# cert3d_rev1.net
KiCad netlist of a schematic drawn in EAGLE
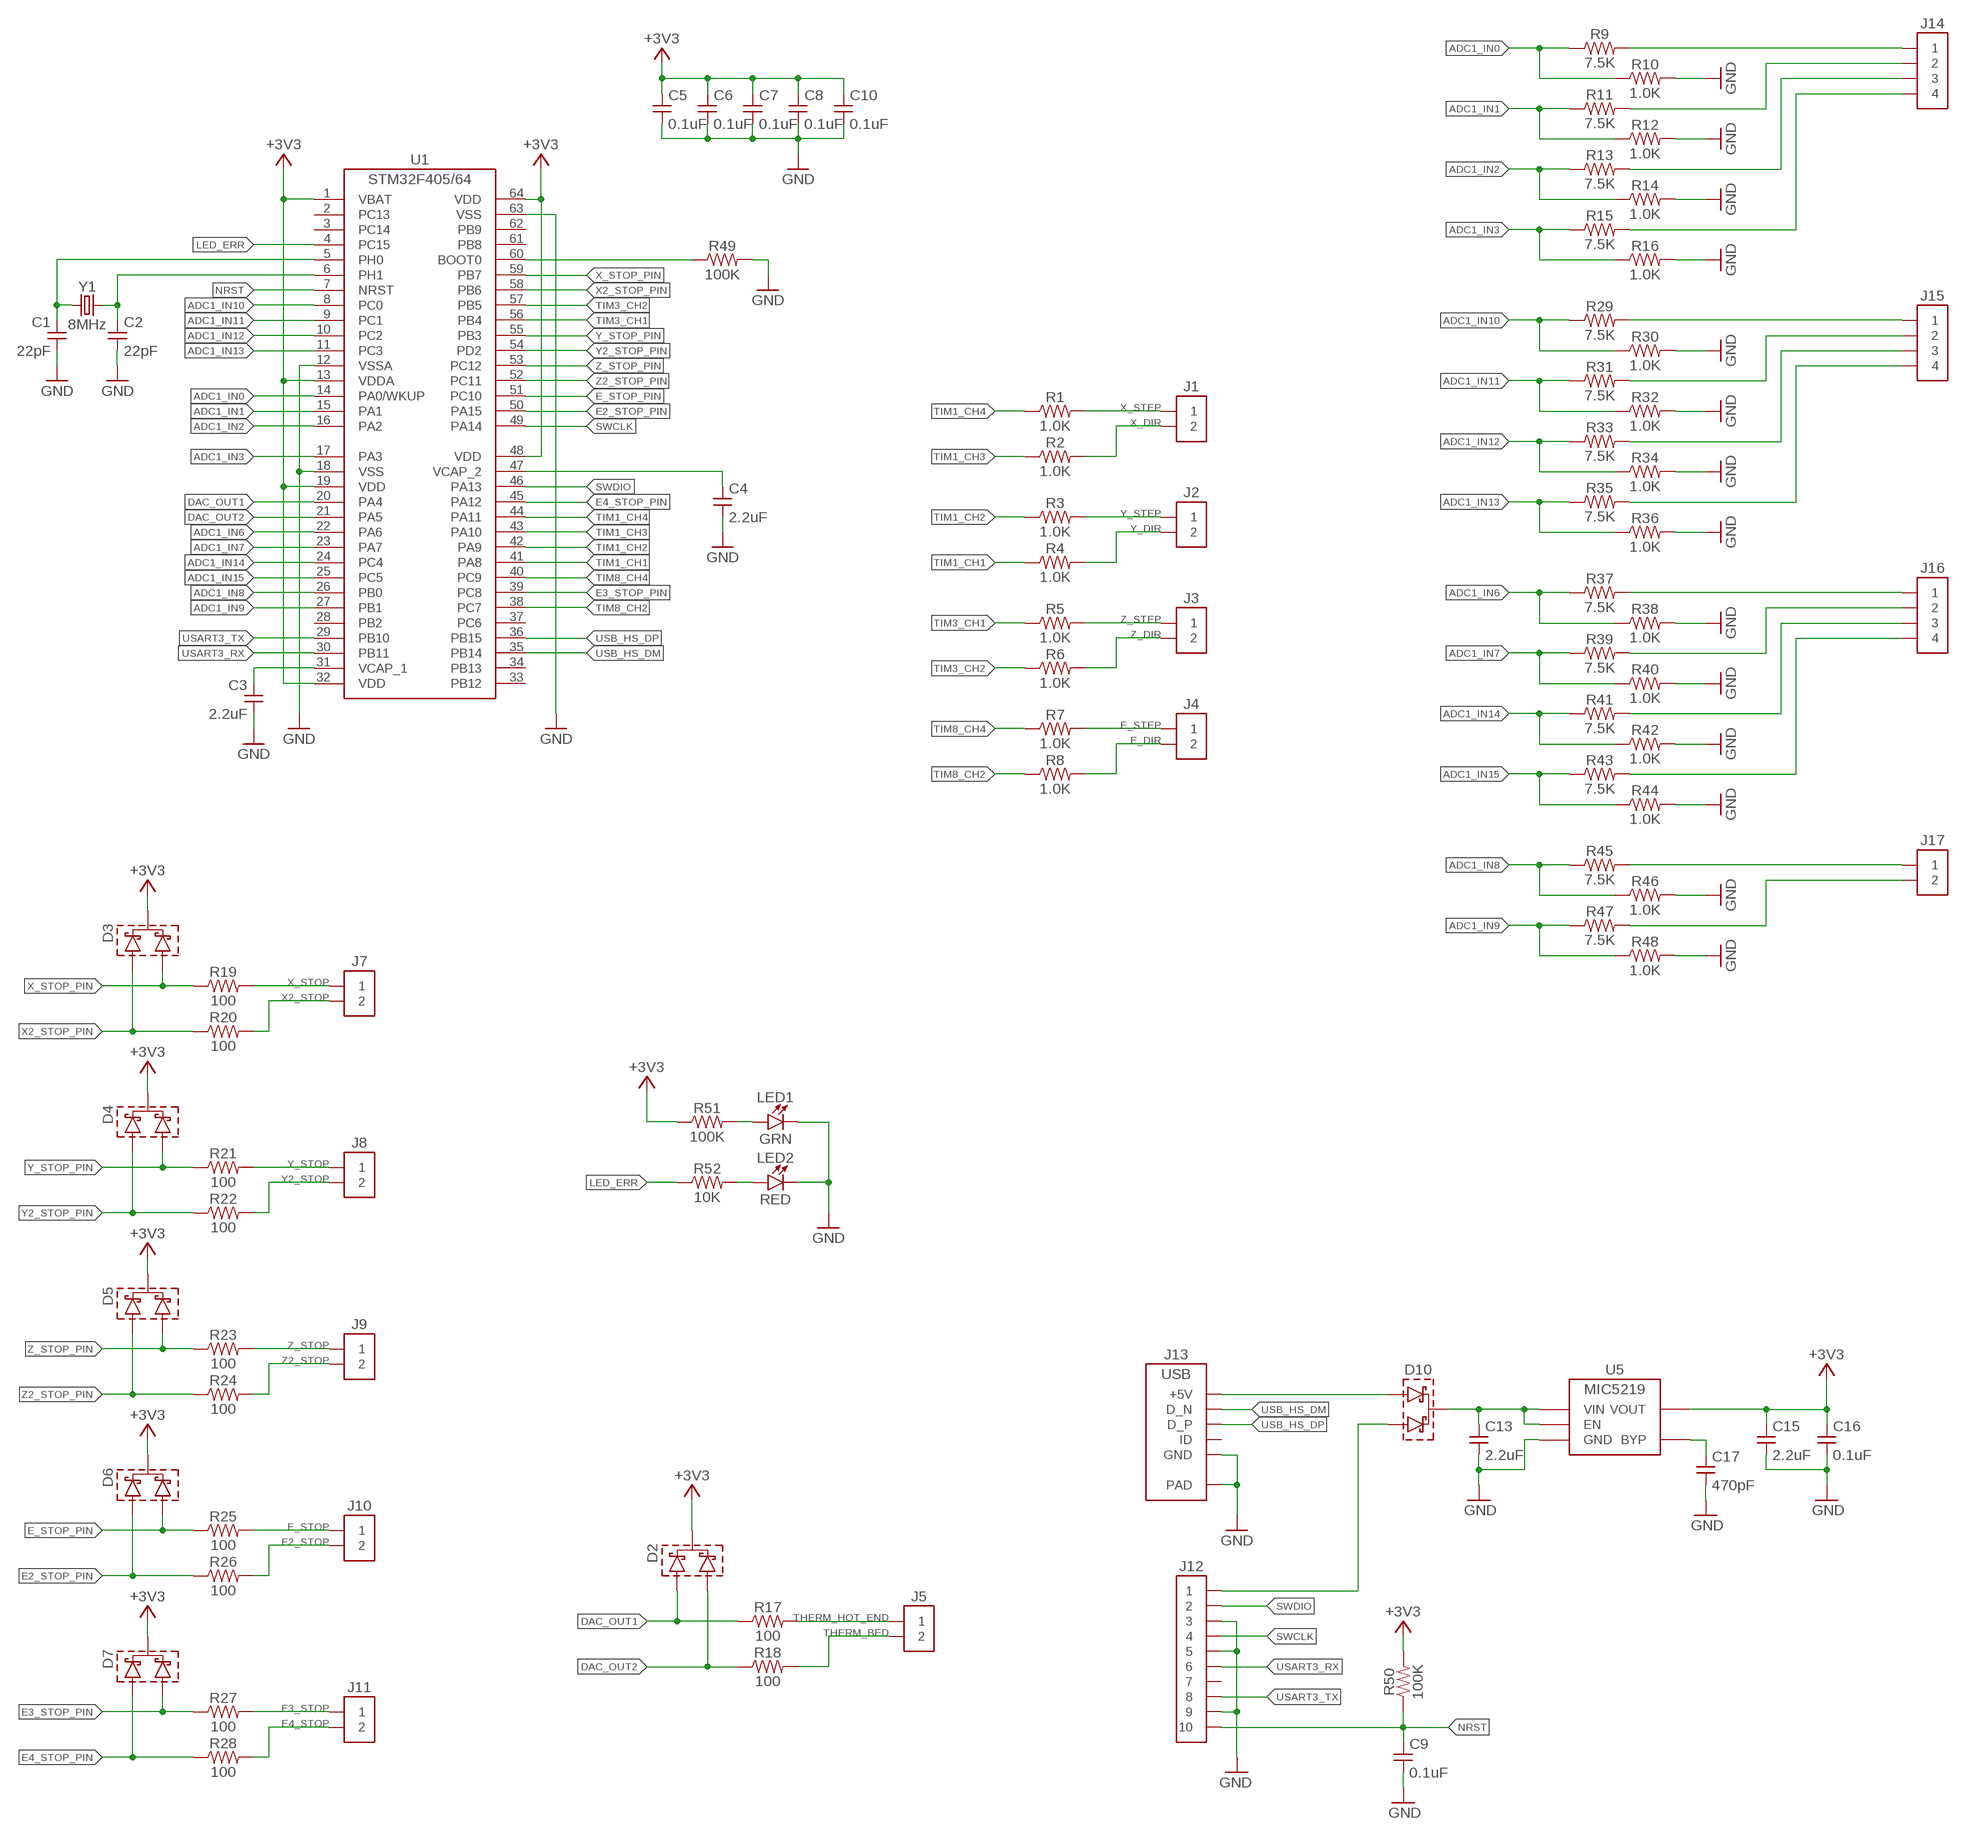
[diagram p0: schematic, sheet 1]

(export (version "E")
  (design (tool "Eeschema 10.0.6"))
  (components
    (comp (ref "C1")
      (value "22pF")
      (footprint "eagle-import:C0805-5MIL")
      (libsource (lib "eagle-import") (part "C_USC0805-5MIL"))
    )
    (comp (ref "C2")
      (value "22pF")
      (footprint "eagle-import:C0805-5MIL")
      (libsource (lib "eagle-import") (part "C_USC0805-5MIL"))
    )
    (comp (ref "C3")
      (value "2.2uF")
      (footprint "eagle-import:C0805-5MIL")
      (libsource (lib "eagle-import") (part "C_USC0805-5MIL"))
    )
    (comp (ref "C4")
      (value "2.2uF")
      (footprint "eagle-import:C0805-5MIL")
      (libsource (lib "eagle-import") (part "C_USC0805-5MIL"))
    )
    (comp (ref "C5")
      (value "0.1uF")
      (footprint "eagle-import:C0805-5MIL")
      (libsource (lib "eagle-import") (part "C_USC0805-5MIL"))
    )
    (comp (ref "C6")
      (value "0.1uF")
      (footprint "eagle-import:C0805-5MIL")
      (libsource (lib "eagle-import") (part "C_USC0805-5MIL"))
    )
    (comp (ref "C7")
      (value "0.1uF")
      (footprint "eagle-import:C0805-5MIL")
      (libsource (lib "eagle-import") (part "C_USC0805-5MIL"))
    )
    (comp (ref "C8")
      (value "0.1uF")
      (footprint "eagle-import:C0805-5MIL")
      (libsource (lib "eagle-import") (part "C_USC0805-5MIL"))
    )
    (comp (ref "C9")
      (value "0.1uF")
      (footprint "eagle-import:C0805-5MIL")
      (libsource (lib "eagle-import") (part "C_USC0805-5MIL"))
    )
    (comp (ref "C10")
      (value "0.1uF")
      (footprint "eagle-import:C0805-5MIL")
      (libsource (lib "eagle-import") (part "C_USC0805-5MIL"))
    )
    (comp (ref "C13")
      (value "2.2uF")
      (footprint "eagle-import:C0805-5MIL")
      (libsource (lib "eagle-import") (part "C_USC0805-5MIL"))
    )
    (comp (ref "C15")
      (value "2.2uF")
      (footprint "eagle-import:C0805-5MIL")
      (libsource (lib "eagle-import") (part "C_USC0805-5MIL"))
    )
    (comp (ref "C16")
      (value "0.1uF")
      (footprint "eagle-import:C0805-5MIL")
      (libsource (lib "eagle-import") (part "C_USC0805-5MIL"))
    )
    (comp (ref "C17")
      (value "470pF")
      (footprint "eagle-import:C0805-5MIL")
      (libsource (lib "eagle-import") (part "C_USC0805-5MIL"))
    )
    (comp (ref "D2")
      (value "SCHOTTKY_DUAL_CCBAT54C")
      (footprint "eagle-import:SOT23-3")
      (libsource (lib "eagle-import") (part "SCHOTTKY_DUAL_CCBAT54C"))
    )
    (comp (ref "D3")
      (value "SCHOTTKY_DUAL_CCBAT54C")
      (footprint "eagle-import:SOT23-3")
      (libsource (lib "eagle-import") (part "SCHOTTKY_DUAL_CCBAT54C"))
    )
    (comp (ref "D4")
      (value "SCHOTTKY_DUAL_CCBAT54C")
      (footprint "eagle-import:SOT23-3")
      (libsource (lib "eagle-import") (part "SCHOTTKY_DUAL_CCBAT54C"))
    )
    (comp (ref "D5")
      (value "SCHOTTKY_DUAL_CCBAT54C")
      (footprint "eagle-import:SOT23-3")
      (libsource (lib "eagle-import") (part "SCHOTTKY_DUAL_CCBAT54C"))
    )
    (comp (ref "D6")
      (value "SCHOTTKY_DUAL_CCBAT54C")
      (footprint "eagle-import:SOT23-3")
      (libsource (lib "eagle-import") (part "SCHOTTKY_DUAL_CCBAT54C"))
    )
    (comp (ref "D7")
      (value "SCHOTTKY_DUAL_CCBAT54C")
      (footprint "eagle-import:SOT23-3")
      (libsource (lib "eagle-import") (part "SCHOTTKY_DUAL_CCBAT54C"))
    )
    (comp (ref "D10")
      (value "SCHOTTKY_DUAL_CCBAT54C")
      (footprint "eagle-import:SOT23-3")
      (libsource (lib "eagle-import") (part "SCHOTTKY_DUAL_CCBAT54C"))
    )
    (comp (ref "J1")
      (value "CONN2TSW-S")
      (footprint "eagle-import:SAM-TSW-102-XX-X-S")
      (libsource (lib "eagle-import") (part "CONN2TSW-S"))
    )
    (comp (ref "J2")
      (value "CONN2TSW-S")
      (footprint "eagle-import:SAM-TSW-102-XX-X-S")
      (libsource (lib "eagle-import") (part "CONN2TSW-S"))
    )
    (comp (ref "J3")
      (value "CONN2TSW-S")
      (footprint "eagle-import:SAM-TSW-102-XX-X-S")
      (libsource (lib "eagle-import") (part "CONN2TSW-S"))
    )
    (comp (ref "J4")
      (value "CONN2TSW-S")
      (footprint "eagle-import:SAM-TSW-102-XX-X-S")
      (libsource (lib "eagle-import") (part "CONN2TSW-S"))
    )
    (comp (ref "J5")
      (value "CONN2TSW-S")
      (footprint "eagle-import:SAM-TSW-102-XX-X-S")
      (libsource (lib "eagle-import") (part "CONN2TSW-S"))
    )
    (comp (ref "J7")
      (value "CONN2TSW-S")
      (footprint "eagle-import:SAM-TSW-102-XX-X-S")
      (libsource (lib "eagle-import") (part "CONN2TSW-S"))
    )
    (comp (ref "J8")
      (value "CONN2TSW-S")
      (footprint "eagle-import:SAM-TSW-102-XX-X-S")
      (libsource (lib "eagle-import") (part "CONN2TSW-S"))
    )
    (comp (ref "J9")
      (value "CONN2TSW-S")
      (footprint "eagle-import:SAM-TSW-102-XX-X-S")
      (libsource (lib "eagle-import") (part "CONN2TSW-S"))
    )
    (comp (ref "J10")
      (value "CONN2TSW-S")
      (footprint "eagle-import:SAM-TSW-102-XX-X-S")
      (libsource (lib "eagle-import") (part "CONN2TSW-S"))
    )
    (comp (ref "J11")
      (value "CONN2TSW-S")
      (footprint "eagle-import:SAM-TSW-102-XX-X-S")
      (libsource (lib "eagle-import") (part "CONN2TSW-S"))
    )
    (comp (ref "J12")
      (value "CONN10CNC-3220-10-0100-00")
      (footprint "eagle-import:CNC-3220-10-0100-00")
      (libsource (lib "eagle-import") (part "CONN10CNC-3220-10-0100-00"))
    )
    (comp (ref "J13")
      (value "USB-5PINTOPVIA")
      (footprint "eagle-import:HIR-ZX62R-B-5P-VIAS")
      (libsource (lib "eagle-import") (part "USB-5PINTOPVIA"))
    )
    (comp (ref "J14")
      (value "CONN4TSW-S")
      (footprint "eagle-import:SAM-TSW-104-XX-X-S")
      (libsource (lib "eagle-import") (part "CONN4TSW-S"))
    )
    (comp (ref "J15")
      (value "CONN4TSW-S")
      (footprint "eagle-import:SAM-TSW-104-XX-X-S")
      (libsource (lib "eagle-import") (part "CONN4TSW-S"))
    )
    (comp (ref "J16")
      (value "CONN4TSW-S")
      (footprint "eagle-import:SAM-TSW-104-XX-X-S")
      (libsource (lib "eagle-import") (part "CONN4TSW-S"))
    )
    (comp (ref "J17")
      (value "CONN2TSW-S")
      (footprint "eagle-import:SAM-TSW-102-XX-X-S")
      (libsource (lib "eagle-import") (part "CONN2TSW-S"))
    )
    (comp (ref "LED1")
      (value "GRN")
      (footprint "eagle-import:CHIPLED0805-SMALL")
      (libsource (lib "eagle-import") (part "LEDCHIPLED0805-SMALL"))
    )
    (comp (ref "LED2")
      (value "RED")
      (footprint "eagle-import:CHIPLED0805-SMALL")
      (libsource (lib "eagle-import") (part "LEDCHIPLED0805-SMALL"))
    )
    (comp (ref "R1")
      (value "1.0K")
      (footprint "eagle-import:RES0805R")
      (libsource (lib "eagle-import") (part "R_US0805R"))
    )
    (comp (ref "R2")
      (value "1.0K")
      (footprint "eagle-import:RES0805R")
      (libsource (lib "eagle-import") (part "R_US0805R"))
    )
    (comp (ref "R3")
      (value "1.0K")
      (footprint "eagle-import:RES0805R")
      (libsource (lib "eagle-import") (part "R_US0805R"))
    )
    (comp (ref "R4")
      (value "1.0K")
      (footprint "eagle-import:RES0805R")
      (libsource (lib "eagle-import") (part "R_US0805R"))
    )
    (comp (ref "R5")
      (value "1.0K")
      (footprint "eagle-import:RES0805R")
      (libsource (lib "eagle-import") (part "R_US0805R"))
    )
    (comp (ref "R6")
      (value "1.0K")
      (footprint "eagle-import:RES0805R")
      (libsource (lib "eagle-import") (part "R_US0805R"))
    )
    (comp (ref "R7")
      (value "1.0K")
      (footprint "eagle-import:RES0805R")
      (libsource (lib "eagle-import") (part "R_US0805R"))
    )
    (comp (ref "R8")
      (value "1.0K")
      (footprint "eagle-import:RES0805R")
      (libsource (lib "eagle-import") (part "R_US0805R"))
    )
    (comp (ref "R9")
      (value "7.5K")
      (footprint "eagle-import:RES0805R-5MIL")
      (libsource (lib "eagle-import") (part "R_USRES0805-5MIL"))
    )
    (comp (ref "R10")
      (value "1.0K")
      (footprint "eagle-import:RES0805R-5MIL")
      (libsource (lib "eagle-import") (part "R_USRES0805-5MIL"))
    )
    (comp (ref "R11")
      (value "7.5K")
      (footprint "eagle-import:RES0805R-5MIL")
      (libsource (lib "eagle-import") (part "R_USRES0805-5MIL"))
    )
    (comp (ref "R12")
      (value "1.0K")
      (footprint "eagle-import:RES0805R-5MIL")
      (libsource (lib "eagle-import") (part "R_USRES0805-5MIL"))
    )
    (comp (ref "R13")
      (value "7.5K")
      (footprint "eagle-import:RES0805R-5MIL")
      (libsource (lib "eagle-import") (part "R_USRES0805-5MIL"))
    )
    (comp (ref "R14")
      (value "1.0K")
      (footprint "eagle-import:RES0805R-5MIL")
      (libsource (lib "eagle-import") (part "R_USRES0805-5MIL"))
    )
    (comp (ref "R15")
      (value "7.5K")
      (footprint "eagle-import:RES0805R-5MIL")
      (libsource (lib "eagle-import") (part "R_USRES0805-5MIL"))
    )
    (comp (ref "R16")
      (value "1.0K")
      (footprint "eagle-import:RES0805R-5MIL")
      (libsource (lib "eagle-import") (part "R_USRES0805-5MIL"))
    )
    (comp (ref "R17")
      (value "100")
      (footprint "eagle-import:RES0805R-5MIL")
      (libsource (lib "eagle-import") (part "R_USRES0805-5MIL"))
    )
    (comp (ref "R18")
      (value "100")
      (footprint "eagle-import:RES0805R-5MIL")
      (libsource (lib "eagle-import") (part "R_USRES0805-5MIL"))
    )
    (comp (ref "R19")
      (value "100")
      (footprint "eagle-import:RES0805R-5MIL")
      (libsource (lib "eagle-import") (part "R_USRES0805-5MIL"))
    )
    (comp (ref "R20")
      (value "100")
      (footprint "eagle-import:RES0805R-5MIL")
      (libsource (lib "eagle-import") (part "R_USRES0805-5MIL"))
    )
    (comp (ref "R21")
      (value "100")
      (footprint "eagle-import:RES0805R-5MIL")
      (libsource (lib "eagle-import") (part "R_USRES0805-5MIL"))
    )
    (comp (ref "R22")
      (value "100")
      (footprint "eagle-import:RES0805R-5MIL")
      (libsource (lib "eagle-import") (part "R_USRES0805-5MIL"))
    )
    (comp (ref "R23")
      (value "100")
      (footprint "eagle-import:RES0805R-5MIL")
      (libsource (lib "eagle-import") (part "R_USRES0805-5MIL"))
    )
    (comp (ref "R24")
      (value "100")
      (footprint "eagle-import:RES0805R-5MIL")
      (libsource (lib "eagle-import") (part "R_USRES0805-5MIL"))
    )
    (comp (ref "R25")
      (value "100")
      (footprint "eagle-import:RES0805R-5MIL")
      (libsource (lib "eagle-import") (part "R_USRES0805-5MIL"))
    )
    (comp (ref "R26")
      (value "100")
      (footprint "eagle-import:RES0805R-5MIL")
      (libsource (lib "eagle-import") (part "R_USRES0805-5MIL"))
    )
    (comp (ref "R27")
      (value "100")
      (footprint "eagle-import:RES0805R-5MIL")
      (libsource (lib "eagle-import") (part "R_USRES0805-5MIL"))
    )
    (comp (ref "R28")
      (value "100")
      (footprint "eagle-import:RES0805R-5MIL")
      (libsource (lib "eagle-import") (part "R_USRES0805-5MIL"))
    )
    (comp (ref "R29")
      (value "7.5K")
      (footprint "eagle-import:RES0805R-5MIL")
      (libsource (lib "eagle-import") (part "R_USRES0805-5MIL"))
    )
    (comp (ref "R30")
      (value "1.0K")
      (footprint "eagle-import:RES0805R-5MIL")
      (libsource (lib "eagle-import") (part "R_USRES0805-5MIL"))
    )
    (comp (ref "R31")
      (value "7.5K")
      (footprint "eagle-import:RES0805R-5MIL")
      (libsource (lib "eagle-import") (part "R_USRES0805-5MIL"))
    )
    (comp (ref "R32")
      (value "1.0K")
      (footprint "eagle-import:RES0805R-5MIL")
      (libsource (lib "eagle-import") (part "R_USRES0805-5MIL"))
    )
    (comp (ref "R33")
      (value "7.5K")
      (footprint "eagle-import:RES0805R-5MIL")
      (libsource (lib "eagle-import") (part "R_USRES0805-5MIL"))
    )
    (comp (ref "R34")
      (value "1.0K")
      (footprint "eagle-import:RES0805R-5MIL")
      (libsource (lib "eagle-import") (part "R_USRES0805-5MIL"))
    )
    (comp (ref "R35")
      (value "7.5K")
      (footprint "eagle-import:RES0805R-5MIL")
      (libsource (lib "eagle-import") (part "R_USRES0805-5MIL"))
    )
    (comp (ref "R36")
      (value "1.0K")
      (footprint "eagle-import:RES0805R-5MIL")
      (libsource (lib "eagle-import") (part "R_USRES0805-5MIL"))
    )
    (comp (ref "R37")
      (value "7.5K")
      (footprint "eagle-import:RES0805R-5MIL")
      (libsource (lib "eagle-import") (part "R_USRES0805-5MIL"))
    )
    (comp (ref "R38")
      (value "1.0K")
      (footprint "eagle-import:RES0805R-5MIL")
      (libsource (lib "eagle-import") (part "R_USRES0805-5MIL"))
    )
    (comp (ref "R39")
      (value "7.5K")
      (footprint "eagle-import:RES0805R-5MIL")
      (libsource (lib "eagle-import") (part "R_USRES0805-5MIL"))
    )
    (comp (ref "R40")
      (value "1.0K")
      (footprint "eagle-import:RES0805R-5MIL")
      (libsource (lib "eagle-import") (part "R_USRES0805-5MIL"))
    )
    (comp (ref "R41")
      (value "7.5K")
      (footprint "eagle-import:RES0805R-5MIL")
      (libsource (lib "eagle-import") (part "R_USRES0805-5MIL"))
    )
    (comp (ref "R42")
      (value "1.0K")
      (footprint "eagle-import:RES0805R-5MIL")
      (libsource (lib "eagle-import") (part "R_USRES0805-5MIL"))
    )
    (comp (ref "R43")
      (value "7.5K")
      (footprint "eagle-import:RES0805R-5MIL")
      (libsource (lib "eagle-import") (part "R_USRES0805-5MIL"))
    )
    (comp (ref "R44")
      (value "1.0K")
      (footprint "eagle-import:RES0805R-5MIL")
      (libsource (lib "eagle-import") (part "R_USRES0805-5MIL"))
    )
    (comp (ref "R45")
      (value "7.5K")
      (footprint "eagle-import:RES0805R-5MIL")
      (libsource (lib "eagle-import") (part "R_USRES0805-5MIL"))
    )
    (comp (ref "R46")
      (value "1.0K")
      (footprint "eagle-import:RES0805R-5MIL")
      (libsource (lib "eagle-import") (part "R_USRES0805-5MIL"))
    )
    (comp (ref "R47")
      (value "7.5K")
      (footprint "eagle-import:RES0805R-5MIL")
      (libsource (lib "eagle-import") (part "R_USRES0805-5MIL"))
    )
    (comp (ref "R48")
      (value "1.0K")
      (footprint "eagle-import:RES0805R-5MIL")
      (libsource (lib "eagle-import") (part "R_USRES0805-5MIL"))
    )
    (comp (ref "R49")
      (value "100K")
      (footprint "eagle-import:RES0805R-5MIL")
      (libsource (lib "eagle-import") (part "R_USRES0805-5MIL"))
    )
    (comp (ref "R50")
      (value "100K")
      (footprint "eagle-import:RES0805R-5MIL")
      (libsource (lib "eagle-import") (part "R_USRES0805-5MIL"))
    )
    (comp (ref "R51")
      (value "100K")
      (footprint "eagle-import:RES0805R-5MIL")
      (libsource (lib "eagle-import") (part "R_USRES0805-5MIL"))
    )
    (comp (ref "R52")
      (value "10K")
      (footprint "eagle-import:RES0805R-5MIL")
      (libsource (lib "eagle-import") (part "R_USRES0805-5MIL"))
    )
    (comp (ref "U1")
      (value "STM32F405/64")
      (footprint "eagle-import:LQFP64-10X10MM")
      (libsource (lib "eagle-import") (part "STM32F405/64"))
    )
    (comp (ref "U5")
      (value "MIC5219")
      (footprint "eagle-import:SOT23-5")
      (libsource (lib "eagle-import") (part "MIC5219"))
    )
    (comp (ref "Y1")
      (value "8MHz")
      (footprint "eagle-import:HC49US")
      (libsource (lib "eagle-import") (part "CRYSTALHC49US"))
    )
  )
  (nets
    (net (code "1") (name "+3V3") (class "Default")
      (node (ref "C10") (pin "1") (pinfunction "1_1") (pintype "passive"))
      (node (ref "C15") (pin "1") (pinfunction "1_1") (pintype "passive"))
      (node (ref "C16") (pin "1") (pinfunction "1_1") (pintype "passive"))
      (node (ref "C5") (pin "1") (pinfunction "1_1") (pintype "passive"))
      (node (ref "C6") (pin "1") (pinfunction "1_1") (pintype "passive"))
      (node (ref "C7") (pin "1") (pinfunction "1_1") (pintype "passive"))
      (node (ref "C8") (pin "1") (pinfunction "1_1") (pintype "passive"))
      (node (ref "D2") (pin "3") (pinfunction "C_3") (pintype "passive"))
      (node (ref "D3") (pin "3") (pinfunction "C_3") (pintype "passive"))
      (node (ref "D4") (pin "3") (pinfunction "C_3") (pintype "passive"))
      (node (ref "D5") (pin "3") (pinfunction "C_3") (pintype "passive"))
      (node (ref "D6") (pin "3") (pinfunction "C_3") (pintype "passive"))
      (node (ref "D7") (pin "3") (pinfunction "C_3") (pintype "passive"))
      (node (ref "R50") (pin "2") (pinfunction "2_2") (pintype "passive"))
      (node (ref "R51") (pin "1") (pinfunction "1_1") (pintype "passive"))
      (node (ref "U1") (pin "1") (pinfunction "VBAT_1") (pintype "bidirectional"))
      (node (ref "U1") (pin "13") (pinfunction "VDDA_13") (pintype "bidirectional"))
      (node (ref "U1") (pin "19") (pinfunction "VDD_19") (pintype "bidirectional"))
      (node (ref "U1") (pin "32") (pinfunction "VDD_32") (pintype "bidirectional"))
      (node (ref "U1") (pin "48") (pinfunction "VDD_48") (pintype "bidirectional"))
      (node (ref "U1") (pin "64") (pinfunction "VDD_64") (pintype "bidirectional"))
      (node (ref "U5") (pin "5") (pinfunction "VOUT_5") (pintype "bidirectional"))
    )
    (net (code "2") (name "/E2_STOP") (class "Default")
      (node (ref "J10") (pin "2") (pinfunction "2_2") (pintype "passive"))
      (node (ref "R26") (pin "2") (pinfunction "2_2") (pintype "passive"))
    )
    (net (code "3") (name "/E3_STOP") (class "Default")
      (node (ref "J11") (pin "1") (pinfunction "1_1") (pintype "passive"))
      (node (ref "R27") (pin "2") (pinfunction "2_2") (pintype "passive"))
    )
    (net (code "4") (name "/E4_STOP") (class "Default")
      (node (ref "J11") (pin "2") (pinfunction "2_2") (pintype "passive"))
      (node (ref "R28") (pin "2") (pinfunction "2_2") (pintype "passive"))
    )
    (net (code "5") (name "/E_DIR") (class "Default")
      (node (ref "J4") (pin "2") (pinfunction "2_2") (pintype "passive"))
      (node (ref "R8") (pin "2") (pinfunction "2_2") (pintype "passive"))
    )
    (net (code "6") (name "/E_STEP") (class "Default")
      (node (ref "J4") (pin "1") (pinfunction "1_1") (pintype "passive"))
      (node (ref "R7") (pin "2") (pinfunction "2_2") (pintype "passive"))
    )
    (net (code "7") (name "/E_STOP") (class "Default")
      (node (ref "J10") (pin "1") (pinfunction "1_1") (pintype "passive"))
      (node (ref "R25") (pin "2") (pinfunction "2_2") (pintype "passive"))
    )
    (net (code "8") (name "/THERM_BED") (class "Default")
      (node (ref "J5") (pin "2") (pinfunction "2_2") (pintype "passive"))
      (node (ref "R18") (pin "2") (pinfunction "2_2") (pintype "passive"))
    )
    (net (code "9") (name "/THERM_HOT_END") (class "Default")
      (node (ref "J5") (pin "1") (pinfunction "1_1") (pintype "passive"))
      (node (ref "R17") (pin "2") (pinfunction "2_2") (pintype "passive"))
    )
    (net (code "10") (name "/X2_STOP") (class "Default")
      (node (ref "J7") (pin "2") (pinfunction "2_2") (pintype "passive"))
      (node (ref "R20") (pin "2") (pinfunction "2_2") (pintype "passive"))
    )
    (net (code "11") (name "/X_DIR") (class "Default")
      (node (ref "J1") (pin "2") (pinfunction "2_2") (pintype "passive"))
      (node (ref "R2") (pin "2") (pinfunction "2_2") (pintype "passive"))
    )
    (net (code "12") (name "/X_STEP") (class "Default")
      (node (ref "J1") (pin "1") (pinfunction "1_1") (pintype "passive"))
      (node (ref "R1") (pin "2") (pinfunction "2_2") (pintype "passive"))
    )
    (net (code "13") (name "/X_STOP") (class "Default")
      (node (ref "J7") (pin "1") (pinfunction "1_1") (pintype "passive"))
      (node (ref "R19") (pin "2") (pinfunction "2_2") (pintype "passive"))
    )
    (net (code "14") (name "/Y2_STOP") (class "Default")
      (node (ref "J8") (pin "2") (pinfunction "2_2") (pintype "passive"))
      (node (ref "R22") (pin "2") (pinfunction "2_2") (pintype "passive"))
    )
    (net (code "15") (name "/Y_DIR") (class "Default")
      (node (ref "J2") (pin "2") (pinfunction "2_2") (pintype "passive"))
      (node (ref "R4") (pin "2") (pinfunction "2_2") (pintype "passive"))
    )
    (net (code "16") (name "/Y_STEP") (class "Default")
      (node (ref "J2") (pin "1") (pinfunction "1_1") (pintype "passive"))
      (node (ref "R3") (pin "2") (pinfunction "2_2") (pintype "passive"))
    )
    (net (code "17") (name "/Y_STOP") (class "Default")
      (node (ref "J8") (pin "1") (pinfunction "1_1") (pintype "passive"))
      (node (ref "R21") (pin "2") (pinfunction "2_2") (pintype "passive"))
    )
    (net (code "18") (name "/Z2_STOP") (class "Default")
      (node (ref "J9") (pin "2") (pinfunction "2_2") (pintype "passive"))
      (node (ref "R24") (pin "2") (pinfunction "2_2") (pintype "passive"))
    )
    (net (code "19") (name "/Z_DIR") (class "Default")
      (node (ref "J3") (pin "2") (pinfunction "2_2") (pintype "passive"))
      (node (ref "R6") (pin "2") (pinfunction "2_2") (pintype "passive"))
    )
    (net (code "20") (name "/Z_STEP") (class "Default")
      (node (ref "J3") (pin "1") (pinfunction "1_1") (pintype "passive"))
      (node (ref "R5") (pin "2") (pinfunction "2_2") (pintype "passive"))
    )
    (net (code "21") (name "/Z_STOP") (class "Default")
      (node (ref "J9") (pin "1") (pinfunction "1_1") (pintype "passive"))
      (node (ref "R23") (pin "2") (pinfunction "2_2") (pintype "passive"))
    )
    (net (code "22") (name "ADC1_IN0") (class "Default")
      (node (ref "R10") (pin "1") (pinfunction "1_1") (pintype "passive"))
      (node (ref "R9") (pin "1") (pinfunction "1_1") (pintype "passive"))
      (node (ref "U1") (pin "14") (pinfunction "PA0/WKUP_14") (pintype "bidirectional"))
    )
    (net (code "23") (name "ADC1_IN1") (class "Default")
      (node (ref "R11") (pin "1") (pinfunction "1_1") (pintype "passive"))
      (node (ref "R12") (pin "1") (pinfunction "1_1") (pintype "passive"))
      (node (ref "U1") (pin "15") (pinfunction "PA1_15") (pintype "bidirectional"))
    )
    (net (code "24") (name "ADC1_IN2") (class "Default")
      (node (ref "R13") (pin "1") (pinfunction "1_1") (pintype "passive"))
      (node (ref "R14") (pin "1") (pinfunction "1_1") (pintype "passive"))
      (node (ref "U1") (pin "16") (pinfunction "PA2_16") (pintype "bidirectional"))
    )
    (net (code "25") (name "ADC1_IN3") (class "Default")
      (node (ref "R15") (pin "1") (pinfunction "1_1") (pintype "passive"))
      (node (ref "R16") (pin "1") (pinfunction "1_1") (pintype "passive"))
      (node (ref "U1") (pin "17") (pinfunction "PA3_17") (pintype "bidirectional"))
    )
    (net (code "26") (name "ADC1_IN6") (class "Default")
      (node (ref "R37") (pin "1") (pinfunction "1_1") (pintype "passive"))
      (node (ref "R38") (pin "1") (pinfunction "1_1") (pintype "passive"))
      (node (ref "U1") (pin "22") (pinfunction "PA6_22") (pintype "bidirectional"))
    )
    (net (code "27") (name "ADC1_IN7") (class "Default")
      (node (ref "R39") (pin "1") (pinfunction "1_1") (pintype "passive"))
      (node (ref "R40") (pin "1") (pinfunction "1_1") (pintype "passive"))
      (node (ref "U1") (pin "23") (pinfunction "PA7_23") (pintype "bidirectional"))
    )
    (net (code "28") (name "ADC1_IN8") (class "Default")
      (node (ref "R45") (pin "1") (pinfunction "1_1") (pintype "passive"))
      (node (ref "R46") (pin "1") (pinfunction "1_1") (pintype "passive"))
      (node (ref "U1") (pin "26") (pinfunction "PB0_26") (pintype "bidirectional"))
    )
    (net (code "29") (name "ADC1_IN9") (class "Default")
      (node (ref "R47") (pin "1") (pinfunction "1_1") (pintype "passive"))
      (node (ref "R48") (pin "1") (pinfunction "1_1") (pintype "passive"))
      (node (ref "U1") (pin "27") (pinfunction "PB1_27") (pintype "bidirectional"))
    )
    (net (code "30") (name "ADC1_IN10") (class "Default")
      (node (ref "R29") (pin "1") (pinfunction "1_1") (pintype "passive"))
      (node (ref "R30") (pin "1") (pinfunction "1_1") (pintype "passive"))
      (node (ref "U1") (pin "8") (pinfunction "PC0_8") (pintype "bidirectional"))
    )
    (net (code "31") (name "ADC1_IN11") (class "Default")
      (node (ref "R31") (pin "1") (pinfunction "1_1") (pintype "passive"))
      (node (ref "R32") (pin "1") (pinfunction "1_1") (pintype "passive"))
      (node (ref "U1") (pin "9") (pinfunction "PC1_9") (pintype "bidirectional"))
    )
    (net (code "32") (name "ADC1_IN12") (class "Default")
      (node (ref "R33") (pin "1") (pinfunction "1_1") (pintype "passive"))
      (node (ref "R34") (pin "1") (pinfunction "1_1") (pintype "passive"))
      (node (ref "U1") (pin "10") (pinfunction "PC2_10") (pintype "bidirectional"))
    )
    (net (code "33") (name "ADC1_IN13") (class "Default")
      (node (ref "R35") (pin "1") (pinfunction "1_1") (pintype "passive"))
      (node (ref "R36") (pin "1") (pinfunction "1_1") (pintype "passive"))
      (node (ref "U1") (pin "11") (pinfunction "PC3_11") (pintype "bidirectional"))
    )
    (net (code "34") (name "ADC1_IN14") (class "Default")
      (node (ref "R41") (pin "1") (pinfunction "1_1") (pintype "passive"))
      (node (ref "R42") (pin "1") (pinfunction "1_1") (pintype "passive"))
      (node (ref "U1") (pin "24") (pinfunction "PC4_24") (pintype "bidirectional"))
    )
    (net (code "35") (name "ADC1_IN15") (class "Default")
      (node (ref "R43") (pin "1") (pinfunction "1_1") (pintype "passive"))
      (node (ref "R44") (pin "1") (pinfunction "1_1") (pintype "passive"))
      (node (ref "U1") (pin "25") (pinfunction "PC5_25") (pintype "bidirectional"))
    )
    (net (code "36") (name "DAC_OUT1") (class "Default")
      (node (ref "D2") (pin "1") (pinfunction "A1_1") (pintype "passive"))
      (node (ref "R17") (pin "1") (pinfunction "1_1") (pintype "passive"))
      (node (ref "U1") (pin "20") (pinfunction "PA4_20") (pintype "bidirectional"))
    )
    (net (code "37") (name "DAC_OUT2") (class "Default")
      (node (ref "D2") (pin "2") (pinfunction "A2_2") (pintype "passive"))
      (node (ref "R18") (pin "1") (pinfunction "1_1") (pintype "passive"))
      (node (ref "U1") (pin "21") (pinfunction "PA5_21") (pintype "bidirectional"))
    )
    (net (code "38") (name "E2_STOP_PIN") (class "Default")
      (node (ref "D6") (pin "1") (pinfunction "A1_1") (pintype "passive"))
      (node (ref "R26") (pin "1") (pinfunction "1_1") (pintype "passive"))
      (node (ref "U1") (pin "50") (pinfunction "PA15_50") (pintype "bidirectional"))
    )
    (net (code "39") (name "E3_STOP_PIN") (class "Default")
      (node (ref "D7") (pin "2") (pinfunction "A2_2") (pintype "passive"))
      (node (ref "R27") (pin "1") (pinfunction "1_1") (pintype "passive"))
      (node (ref "U1") (pin "39") (pinfunction "PC8_39") (pintype "bidirectional"))
    )
    (net (code "40") (name "E4_STOP_PIN") (class "Default")
      (node (ref "D7") (pin "1") (pinfunction "A1_1") (pintype "passive"))
      (node (ref "R28") (pin "1") (pinfunction "1_1") (pintype "passive"))
      (node (ref "U1") (pin "45") (pinfunction "PA12_45") (pintype "bidirectional"))
    )
    (net (code "41") (name "E_STOP_PIN") (class "Default")
      (node (ref "D6") (pin "2") (pinfunction "A2_2") (pintype "passive"))
      (node (ref "R25") (pin "1") (pinfunction "1_1") (pintype "passive"))
      (node (ref "U1") (pin "51") (pinfunction "PC10_51") (pintype "bidirectional"))
    )
    (net (code "42") (name "GND") (class "Default")
      (node (ref "C1") (pin "2") (pinfunction "2_2") (pintype "passive"))
      (node (ref "C10") (pin "2") (pinfunction "2_2") (pintype "passive"))
      (node (ref "C13") (pin "2") (pinfunction "2_2") (pintype "passive"))
      (node (ref "C15") (pin "2") (pinfunction "2_2") (pintype "passive"))
      (node (ref "C16") (pin "2") (pinfunction "2_2") (pintype "passive"))
      (node (ref "C17") (pin "2") (pinfunction "2_2") (pintype "passive"))
      (node (ref "C2") (pin "2") (pinfunction "2_2") (pintype "passive"))
      (node (ref "C3") (pin "2") (pinfunction "2_2") (pintype "passive"))
      (node (ref "C4") (pin "2") (pinfunction "2_2") (pintype "passive"))
      (node (ref "C5") (pin "2") (pinfunction "2_2") (pintype "passive"))
      (node (ref "C6") (pin "2") (pinfunction "2_2") (pintype "passive"))
      (node (ref "C7") (pin "2") (pinfunction "2_2") (pintype "passive"))
      (node (ref "C8") (pin "2") (pinfunction "2_2") (pintype "passive"))
      (node (ref "C9") (pin "2") (pinfunction "2_2") (pintype "passive"))
      (node (ref "J12") (pin "3") (pinfunction "3_3") (pintype "passive"))
      (node (ref "J12") (pin "5") (pinfunction "5_5") (pintype "passive"))
      (node (ref "J12") (pin "9") (pinfunction "9_9") (pintype "passive"))
      (node (ref "J13") (pin "5") (pinfunction "GND_5") (pintype "bidirectional"))
      (node (ref "J13") (pin "PAD@1") (pinfunction "PAD_PAD@1") (pintype "bidirectional"))
      (node (ref "J13") (pin "PAD@10") (pinfunction "PAD_PAD@10") (pintype "bidirectional"))
      (node (ref "J13") (pin "PAD@11") (pinfunction "PAD_PAD@11") (pintype "bidirectional"))
      (node (ref "J13") (pin "PAD@12") (pinfunction "PAD_PAD@12") (pintype "bidirectional"))
      (node (ref "J13") (pin "PAD@2") (pinfunction "PAD_PAD@2") (pintype "bidirectional"))
      (node (ref "J13") (pin "PAD@3") (pinfunction "PAD_PAD@3") (pintype "bidirectional"))
      (node (ref "J13") (pin "PAD@4") (pinfunction "PAD_PAD@4") (pintype "bidirectional"))
      (node (ref "J13") (pin "PAD@5") (pinfunction "PAD_PAD@5") (pintype "bidirectional"))
      (node (ref "J13") (pin "PAD@6") (pinfunction "PAD_PAD@6") (pintype "bidirectional"))
      (node (ref "J13") (pin "PAD@7") (pinfunction "PAD_PAD@7") (pintype "bidirectional"))
      (node (ref "J13") (pin "PAD@8") (pinfunction "PAD_PAD@8") (pintype "bidirectional"))
      (node (ref "J13") (pin "PAD@9") (pinfunction "PAD_PAD@9") (pintype "bidirectional"))
      (node (ref "LED1") (pin "C") (pinfunction "C_C") (pintype "passive"))
      (node (ref "LED2") (pin "C") (pinfunction "C_C") (pintype "passive"))
      (node (ref "R10") (pin "2") (pinfunction "2_2") (pintype "passive"))
      (node (ref "R12") (pin "2") (pinfunction "2_2") (pintype "passive"))
      (node (ref "R14") (pin "2") (pinfunction "2_2") (pintype "passive"))
      (node (ref "R16") (pin "2") (pinfunction "2_2") (pintype "passive"))
      (node (ref "R30") (pin "2") (pinfunction "2_2") (pintype "passive"))
      (node (ref "R32") (pin "2") (pinfunction "2_2") (pintype "passive"))
      (node (ref "R34") (pin "2") (pinfunction "2_2") (pintype "passive"))
      (node (ref "R36") (pin "2") (pinfunction "2_2") (pintype "passive"))
      (node (ref "R38") (pin "2") (pinfunction "2_2") (pintype "passive"))
      (node (ref "R40") (pin "2") (pinfunction "2_2") (pintype "passive"))
      (node (ref "R42") (pin "2") (pinfunction "2_2") (pintype "passive"))
      (node (ref "R44") (pin "2") (pinfunction "2_2") (pintype "passive"))
      (node (ref "R46") (pin "2") (pinfunction "2_2") (pintype "passive"))
      (node (ref "R48") (pin "2") (pinfunction "2_2") (pintype "passive"))
      (node (ref "R49") (pin "2") (pinfunction "2_2") (pintype "passive"))
      (node (ref "U1") (pin "12") (pinfunction "VSSA_12") (pintype "bidirectional"))
      (node (ref "U1") (pin "18") (pinfunction "VSS_18") (pintype "bidirectional"))
      (node (ref "U1") (pin "63") (pinfunction "VSS_63") (pintype "bidirectional"))
      (node (ref "U5") (pin "2") (pinfunction "GND_2") (pintype "bidirectional"))
    )
    (net (code "43") (name "LED_ERR") (class "Default")
      (node (ref "R52") (pin "1") (pinfunction "1_1") (pintype "passive"))
      (node (ref "U1") (pin "4") (pinfunction "PC15_4") (pintype "bidirectional"))
    )
    (net (code "44") (name "NRST") (class "Default")
      (node (ref "C9") (pin "1") (pinfunction "1_1") (pintype "passive"))
      (node (ref "J12") (pin "10") (pinfunction "10_10") (pintype "passive"))
      (node (ref "R50") (pin "1") (pinfunction "1_1") (pintype "passive"))
      (node (ref "U1") (pin "7") (pinfunction "NRST_7") (pintype "bidirectional"))
    )
    (net (code "45") (name "Net-(D10-A1)") (class "Default")
      (node (ref "D10") (pin "1") (pinfunction "A1_1") (pintype "passive"))
      (node (ref "J13") (pin "1") (pinfunction "+5V_1") (pintype "bidirectional"))
    )
    (net (code "46") (name "Net-(D10-A2)") (class "Default")
      (node (ref "D10") (pin "2") (pinfunction "A2_2") (pintype "passive"))
      (node (ref "J12") (pin "1") (pinfunction "1_1") (pintype "passive"))
    )
    (net (code "47") (name "Net-(D10-C)") (class "Default")
      (node (ref "C13") (pin "1") (pinfunction "1_1") (pintype "passive"))
      (node (ref "D10") (pin "3") (pinfunction "C_3") (pintype "passive"))
      (node (ref "U5") (pin "1") (pinfunction "VIN_1") (pintype "bidirectional"))
      (node (ref "U5") (pin "3") (pinfunction "EN_3") (pintype "bidirectional"))
    )
    (net (code "48") (name "Net-(J14-Pad1)") (class "Default")
      (node (ref "J14") (pin "1") (pinfunction "1_1") (pintype "passive"))
      (node (ref "R9") (pin "2") (pinfunction "2_2") (pintype "passive"))
    )
    (net (code "49") (name "Net-(J14-Pad2)") (class "Default")
      (node (ref "J14") (pin "2") (pinfunction "2_2") (pintype "passive"))
      (node (ref "R11") (pin "2") (pinfunction "2_2") (pintype "passive"))
    )
    (net (code "50") (name "Net-(J14-Pad3)") (class "Default")
      (node (ref "J14") (pin "3") (pinfunction "3_3") (pintype "passive"))
      (node (ref "R13") (pin "2") (pinfunction "2_2") (pintype "passive"))
    )
    (net (code "51") (name "Net-(J14-Pad4)") (class "Default")
      (node (ref "J14") (pin "4") (pinfunction "4_4") (pintype "passive"))
      (node (ref "R15") (pin "2") (pinfunction "2_2") (pintype "passive"))
    )
    (net (code "52") (name "Net-(J15-Pad1)") (class "Default")
      (node (ref "J15") (pin "1") (pinfunction "1_1") (pintype "passive"))
      (node (ref "R29") (pin "2") (pinfunction "2_2") (pintype "passive"))
    )
    (net (code "53") (name "Net-(J15-Pad2)") (class "Default")
      (node (ref "J15") (pin "2") (pinfunction "2_2") (pintype "passive"))
      (node (ref "R31") (pin "2") (pinfunction "2_2") (pintype "passive"))
    )
    (net (code "54") (name "Net-(J15-Pad3)") (class "Default")
      (node (ref "J15") (pin "3") (pinfunction "3_3") (pintype "passive"))
      (node (ref "R33") (pin "2") (pinfunction "2_2") (pintype "passive"))
    )
    (net (code "55") (name "Net-(J15-Pad4)") (class "Default")
      (node (ref "J15") (pin "4") (pinfunction "4_4") (pintype "passive"))
      (node (ref "R35") (pin "2") (pinfunction "2_2") (pintype "passive"))
    )
    (net (code "56") (name "Net-(J16-Pad1)") (class "Default")
      (node (ref "J16") (pin "1") (pinfunction "1_1") (pintype "passive"))
      (node (ref "R37") (pin "2") (pinfunction "2_2") (pintype "passive"))
    )
    (net (code "57") (name "Net-(J16-Pad2)") (class "Default")
      (node (ref "J16") (pin "2") (pinfunction "2_2") (pintype "passive"))
      (node (ref "R39") (pin "2") (pinfunction "2_2") (pintype "passive"))
    )
    (net (code "58") (name "Net-(J16-Pad3)") (class "Default")
      (node (ref "J16") (pin "3") (pinfunction "3_3") (pintype "passive"))
      (node (ref "R41") (pin "2") (pinfunction "2_2") (pintype "passive"))
    )
    (net (code "59") (name "Net-(J16-Pad4)") (class "Default")
      (node (ref "J16") (pin "4") (pinfunction "4_4") (pintype "passive"))
      (node (ref "R43") (pin "2") (pinfunction "2_2") (pintype "passive"))
    )
    (net (code "60") (name "Net-(J17-Pad1)") (class "Default")
      (node (ref "J17") (pin "1") (pinfunction "1_1") (pintype "passive"))
      (node (ref "R45") (pin "2") (pinfunction "2_2") (pintype "passive"))
    )
    (net (code "61") (name "Net-(J17-Pad2)") (class "Default")
      (node (ref "J17") (pin "2") (pinfunction "2_2") (pintype "passive"))
      (node (ref "R47") (pin "2") (pinfunction "2_2") (pintype "passive"))
    )
    (net (code "62") (name "Net-(LED1-PadA)") (class "Default")
      (node (ref "LED1") (pin "A") (pinfunction "A_A") (pintype "passive"))
      (node (ref "R51") (pin "2") (pinfunction "2_2") (pintype "passive"))
    )
    (net (code "63") (name "Net-(LED2-PadA)") (class "Default")
      (node (ref "LED2") (pin "A") (pinfunction "A_A") (pintype "passive"))
      (node (ref "R52") (pin "2") (pinfunction "2_2") (pintype "passive"))
    )
    (net (code "64") (name "Net-(U1-BOOT0)") (class "Default")
      (node (ref "R49") (pin "1") (pinfunction "1_1") (pintype "passive"))
      (node (ref "U1") (pin "60") (pinfunction "BOOT0_60") (pintype "bidirectional"))
    )
    (net (code "65") (name "Net-(U1-PH0)") (class "Default")
      (node (ref "C1") (pin "1") (pinfunction "1_1") (pintype "passive"))
      (node (ref "U1") (pin "5") (pinfunction "PH0_5") (pintype "bidirectional"))
      (node (ref "Y1") (pin "1") (pinfunction "1_1") (pintype "passive"))
    )
    (net (code "66") (name "Net-(U1-PH1)") (class "Default")
      (node (ref "C2") (pin "1") (pinfunction "1_1") (pintype "passive"))
      (node (ref "U1") (pin "6") (pinfunction "PH1_6") (pintype "bidirectional"))
      (node (ref "Y1") (pin "2") (pinfunction "2_2") (pintype "passive"))
    )
    (net (code "67") (name "Net-(U1-VCAP_1)") (class "Default")
      (node (ref "C3") (pin "1") (pinfunction "1_1") (pintype "passive"))
      (node (ref "U1") (pin "31") (pinfunction "VCAP_1_31") (pintype "bidirectional"))
    )
    (net (code "68") (name "Net-(U1-VCAP_2)") (class "Default")
      (node (ref "C4") (pin "1") (pinfunction "1_1") (pintype "passive"))
      (node (ref "U1") (pin "47") (pinfunction "VCAP_2_47") (pintype "bidirectional"))
    )
    (net (code "69") (name "Net-(U5-BYP)") (class "Default")
      (node (ref "C17") (pin "1") (pinfunction "1_1") (pintype "passive"))
      (node (ref "U5") (pin "4") (pinfunction "BYP_4") (pintype "bidirectional"))
    )
    (net (code "70") (name "SWCLK") (class "Default")
      (node (ref "J12") (pin "4") (pinfunction "4_4") (pintype "passive"))
      (node (ref "U1") (pin "49") (pinfunction "PA14_49") (pintype "bidirectional"))
    )
    (net (code "71") (name "SWDIO") (class "Default")
      (node (ref "J12") (pin "2") (pinfunction "2_2") (pintype "passive"))
      (node (ref "U1") (pin "46") (pinfunction "PA13_46") (pintype "bidirectional"))
    )
    (net (code "72") (name "TIM1_CH1") (class "Default")
      (node (ref "R4") (pin "1") (pinfunction "1_1") (pintype "passive"))
      (node (ref "U1") (pin "41") (pinfunction "PA8_41") (pintype "bidirectional"))
    )
    (net (code "73") (name "TIM1_CH2") (class "Default")
      (node (ref "R3") (pin "1") (pinfunction "1_1") (pintype "passive"))
      (node (ref "U1") (pin "42") (pinfunction "PA9_42") (pintype "bidirectional"))
    )
    (net (code "74") (name "TIM1_CH3") (class "Default")
      (node (ref "R2") (pin "1") (pinfunction "1_1") (pintype "passive"))
      (node (ref "U1") (pin "43") (pinfunction "PA10_43") (pintype "bidirectional"))
    )
    (net (code "75") (name "TIM1_CH4") (class "Default")
      (node (ref "R1") (pin "1") (pinfunction "1_1") (pintype "passive"))
      (node (ref "U1") (pin "44") (pinfunction "PA11_44") (pintype "bidirectional"))
    )
    (net (code "76") (name "TIM3_CH1") (class "Default")
      (node (ref "R5") (pin "1") (pinfunction "1_1") (pintype "passive"))
      (node (ref "U1") (pin "56") (pinfunction "PB4_56") (pintype "bidirectional"))
    )
    (net (code "77") (name "TIM3_CH2") (class "Default")
      (node (ref "R6") (pin "1") (pinfunction "1_1") (pintype "passive"))
      (node (ref "U1") (pin "57") (pinfunction "PB5_57") (pintype "bidirectional"))
    )
    (net (code "78") (name "TIM8_CH2") (class "Default")
      (node (ref "R8") (pin "1") (pinfunction "1_1") (pintype "passive"))
      (node (ref "U1") (pin "38") (pinfunction "PC7_38") (pintype "bidirectional"))
    )
    (net (code "79") (name "TIM8_CH4") (class "Default")
      (node (ref "R7") (pin "1") (pinfunction "1_1") (pintype "passive"))
      (node (ref "U1") (pin "40") (pinfunction "PC9_40") (pintype "bidirectional"))
    )
    (net (code "80") (name "USART3_RX") (class "Default")
      (node (ref "J12") (pin "6") (pinfunction "6_6") (pintype "passive"))
      (node (ref "U1") (pin "30") (pinfunction "PB11_30") (pintype "bidirectional"))
    )
    (net (code "81") (name "USART3_TX") (class "Default")
      (node (ref "J12") (pin "8") (pinfunction "8_8") (pintype "passive"))
      (node (ref "U1") (pin "29") (pinfunction "PB10_29") (pintype "bidirectional"))
    )
    (net (code "82") (name "USB_HS_DM") (class "Default")
      (node (ref "J13") (pin "2") (pinfunction "D_N_2") (pintype "bidirectional"))
      (node (ref "U1") (pin "35") (pinfunction "PB14_35") (pintype "bidirectional"))
    )
    (net (code "83") (name "USB_HS_DP") (class "Default")
      (node (ref "J13") (pin "3") (pinfunction "D_P_3") (pintype "bidirectional"))
      (node (ref "U1") (pin "36") (pinfunction "PB15_36") (pintype "bidirectional"))
    )
    (net (code "84") (name "X2_STOP_PIN") (class "Default")
      (node (ref "D3") (pin "1") (pinfunction "A1_1") (pintype "passive"))
      (node (ref "R20") (pin "1") (pinfunction "1_1") (pintype "passive"))
      (node (ref "U1") (pin "58") (pinfunction "PB6_58") (pintype "bidirectional"))
    )
    (net (code "85") (name "X_STOP_PIN") (class "Default")
      (node (ref "D3") (pin "2") (pinfunction "A2_2") (pintype "passive"))
      (node (ref "R19") (pin "1") (pinfunction "1_1") (pintype "passive"))
      (node (ref "U1") (pin "59") (pinfunction "PB7_59") (pintype "bidirectional"))
    )
    (net (code "86") (name "Y2_STOP_PIN") (class "Default")
      (node (ref "D4") (pin "1") (pinfunction "A1_1") (pintype "passive"))
      (node (ref "R22") (pin "1") (pinfunction "1_1") (pintype "passive"))
      (node (ref "U1") (pin "54") (pinfunction "PD2_54") (pintype "bidirectional"))
    )
    (net (code "87") (name "Y_STOP_PIN") (class "Default")
      (node (ref "D4") (pin "2") (pinfunction "A2_2") (pintype "passive"))
      (node (ref "R21") (pin "1") (pinfunction "1_1") (pintype "passive"))
      (node (ref "U1") (pin "55") (pinfunction "PB3_55") (pintype "bidirectional"))
    )
    (net (code "88") (name "Z2_STOP_PIN") (class "Default")
      (node (ref "D5") (pin "1") (pinfunction "A1_1") (pintype "passive"))
      (node (ref "R24") (pin "1") (pinfunction "1_1") (pintype "passive"))
      (node (ref "U1") (pin "52") (pinfunction "PC11_52") (pintype "bidirectional"))
    )
    (net (code "89") (name "Z_STOP_PIN") (class "Default")
      (node (ref "D5") (pin "2") (pinfunction "A2_2") (pintype "passive"))
      (node (ref "R23") (pin "1") (pinfunction "1_1") (pintype "passive"))
      (node (ref "U1") (pin "53") (pinfunction "PC12_53") (pintype "bidirectional"))
    )
    (net (code "90") (name "unconnected-(J12-Pad7)") (class "Default")
      (node (ref "J12") (pin "7") (pinfunction "7_7") (pintype "passive"))
    )
    (net (code "91") (name "unconnected-(J13-ID-Pad4)") (class "Default")
      (node (ref "J13") (pin "4") (pinfunction "ID_4") (pintype "bidirectional"))
    )
    (net (code "92") (name "unconnected-(U1-PB2-Pad28)") (class "Default")
      (node (ref "U1") (pin "28") (pinfunction "PB2_28") (pintype "bidirectional"))
    )
    (net (code "93") (name "unconnected-(U1-PB8-Pad61)") (class "Default")
      (node (ref "U1") (pin "61") (pinfunction "PB8_61") (pintype "bidirectional"))
    )
    (net (code "94") (name "unconnected-(U1-PB9-Pad62)") (class "Default")
      (node (ref "U1") (pin "62") (pinfunction "PB9_62") (pintype "bidirectional"))
    )
    (net (code "95") (name "unconnected-(U1-PB12-Pad33)") (class "Default")
      (node (ref "U1") (pin "33") (pinfunction "PB12_33") (pintype "bidirectional"))
    )
    (net (code "96") (name "unconnected-(U1-PB13-Pad34)") (class "Default")
      (node (ref "U1") (pin "34") (pinfunction "PB13_34") (pintype "bidirectional"))
    )
    (net (code "97") (name "unconnected-(U1-PC6-Pad37)") (class "Default")
      (node (ref "U1") (pin "37") (pinfunction "PC6_37") (pintype "bidirectional"))
    )
    (net (code "98") (name "unconnected-(U1-PC13-Pad2)") (class "Default")
      (node (ref "U1") (pin "2") (pinfunction "PC13_2") (pintype "bidirectional"))
    )
    (net (code "99") (name "unconnected-(U1-PC14-Pad3)") (class "Default")
      (node (ref "U1") (pin "3") (pinfunction "PC14_3") (pintype "bidirectional"))
    )
  )
)
